# PandaSat_Payload.net
KiCad netlist of a schematic drawn in EAGLE
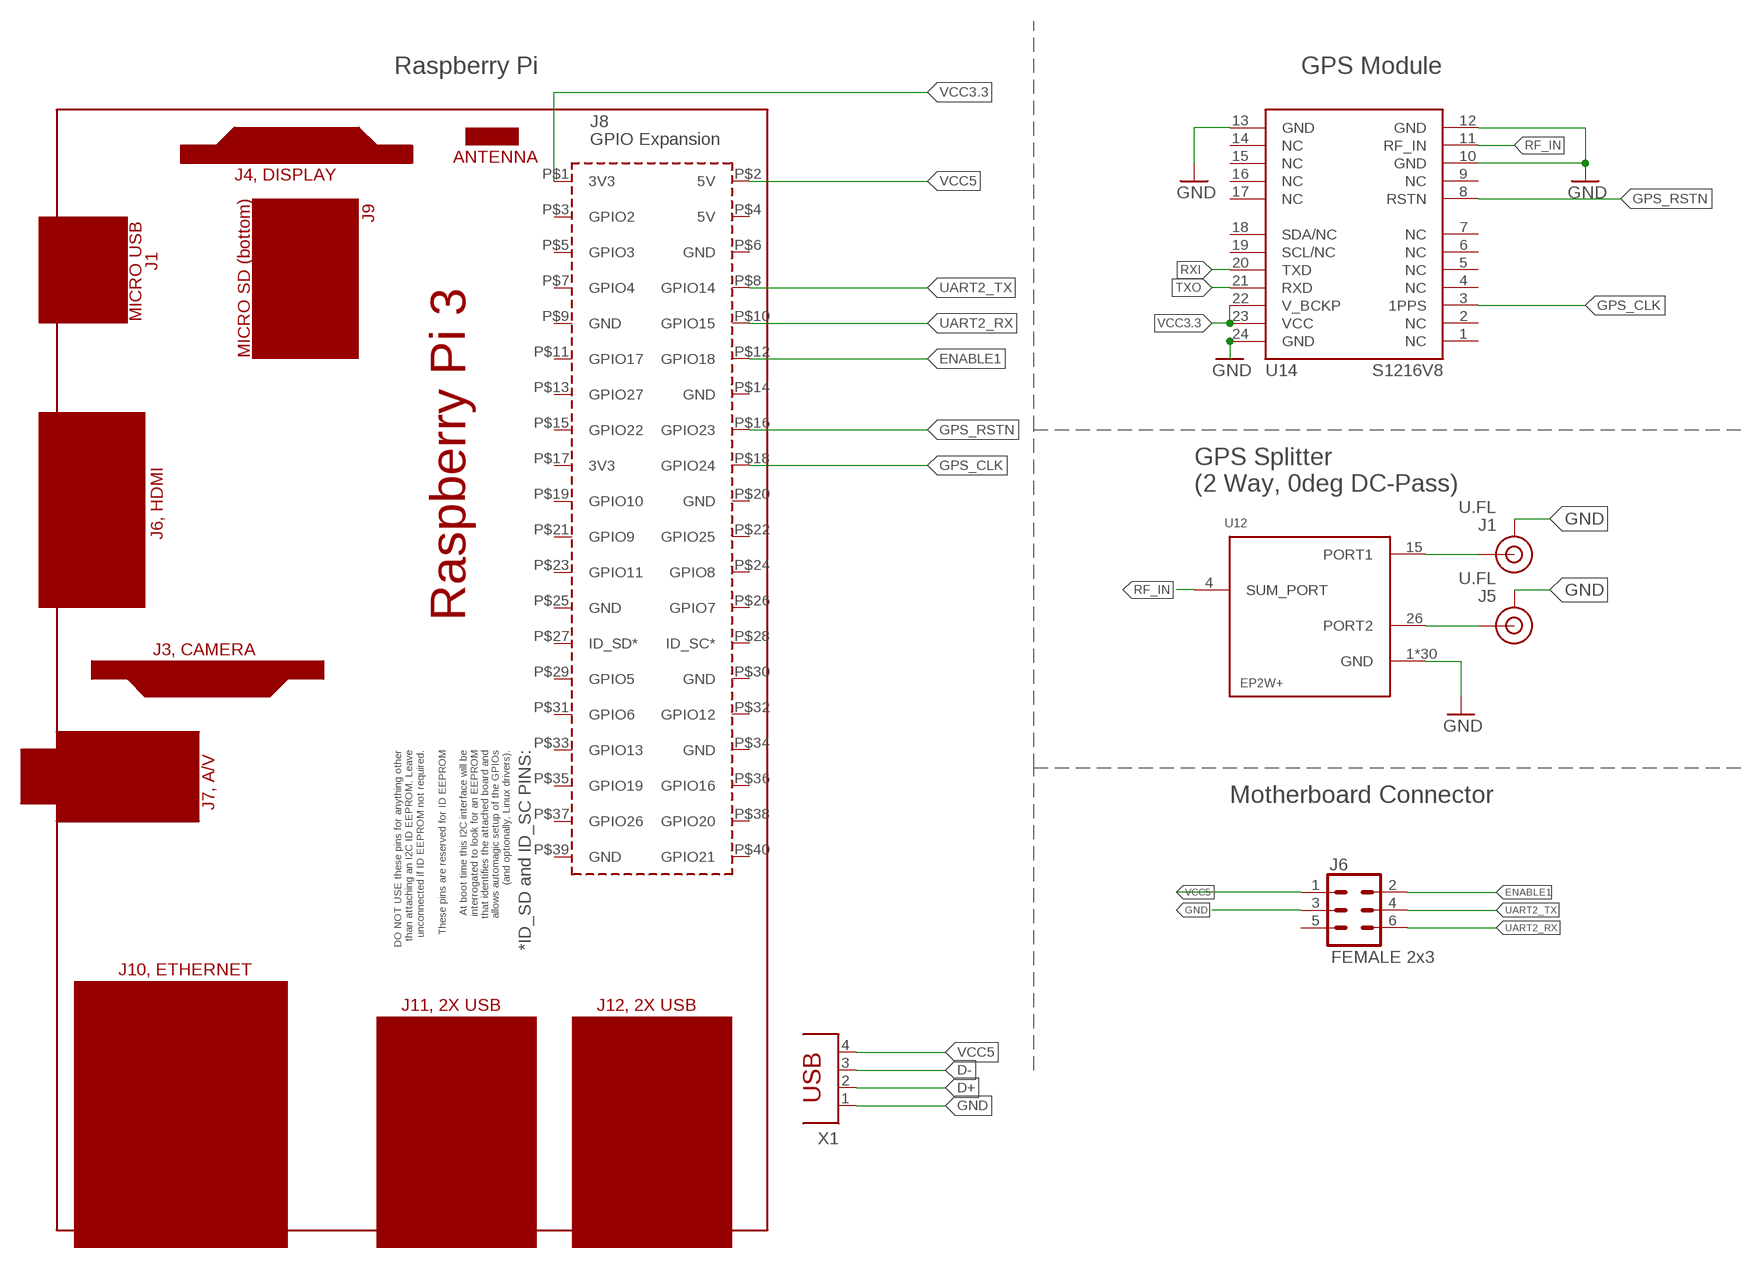
[diagram p0: schematic, sheet 1]
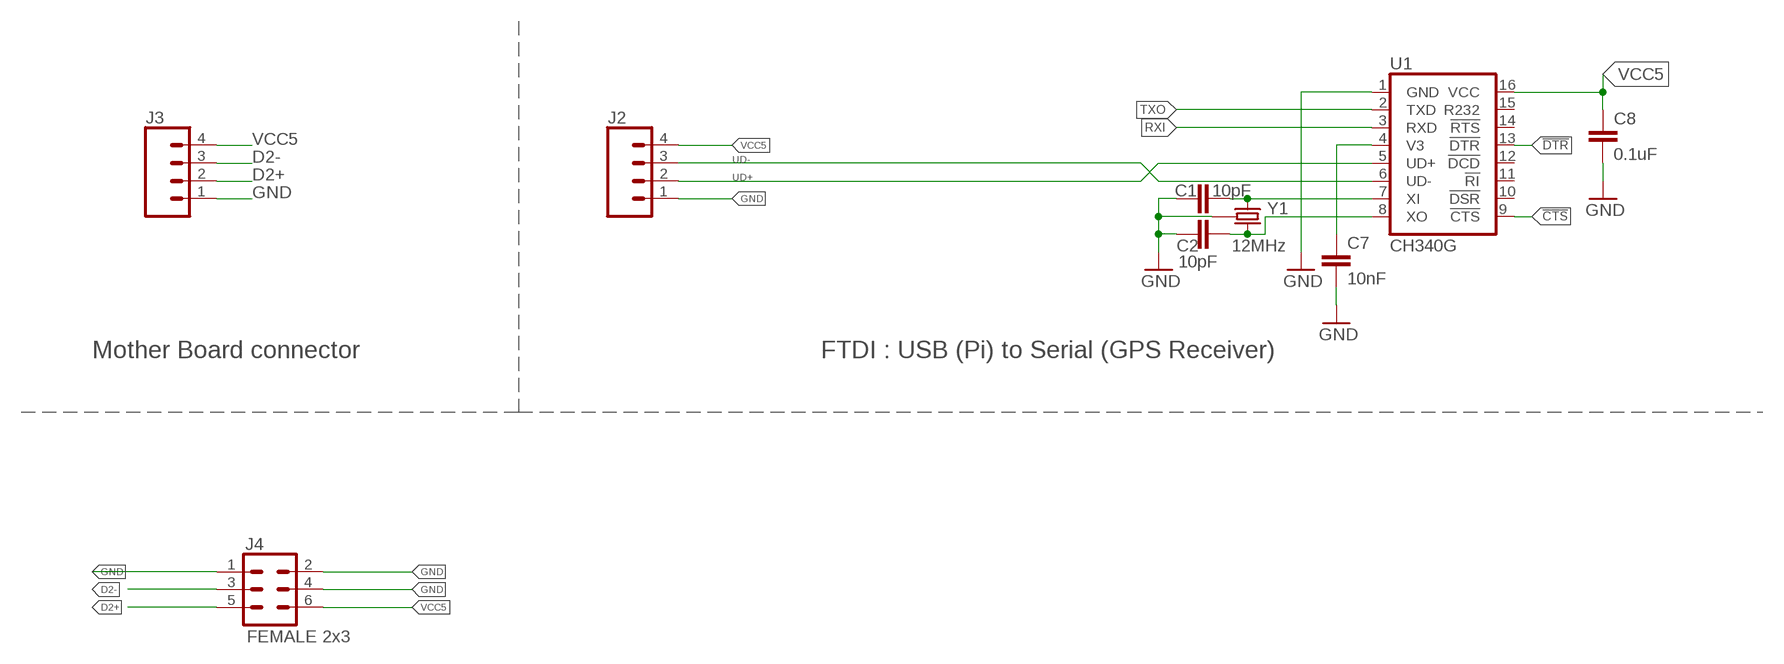
[diagram p1: schematic, sheet 2]

(export (version "E")
  (design (tool "Eeschema 10.0.6"))
  (components
    (comp (ref "J1")
      (value "U.FL")
      (footprint "eagle-import:U.FL")
      (libsource (lib "eagle-import") (part "U.FL2PIN"))
    )
    (comp (ref "J5")
      (value "U.FL")
      (footprint "eagle-import:U.FL")
      (libsource (lib "eagle-import") (part "U.FL2PIN"))
    )
    (comp (ref "J6")
      (value "FEMALE 2x3")
      (footprint "eagle-import:2X3")
      (libsource (lib "eagle-import") (part "CONN_03X2FEMALE"))
    )
    (comp (ref "PCB1")
      (value "RPI3RPI3")
      (footprint "eagle-import:RPI3")
      (libsource (lib "eagle-import") (part "RPI3RPI3"))
    )
    (comp (ref "U12")
      (value "EP2W+")
      (footprint "eagle-import:QFN32-5X5MM")
      (libsource (lib "eagle-import") (part "EP2W+"))
    )
    (comp (ref "U14")
      (value "S1216V8")
      (footprint "eagle-import:S1216_24PIN_PACKAGE")
      (libsource (lib "eagle-import") (part "S1216V8"))
    )
    (comp (ref "X1")
      (value "PN87520")
      (footprint "eagle-import:PN87520")
      (libsource (lib "eagle-import") (part "PN87520"))
    )
    (comp (ref "C1")
      (value "10pF")
      (footprint "eagle-import:0603-CAP")
      (libsource (lib "eagle-import") (part "10PF-50V-5%(0603)"))
    )
    (comp (ref "C2")
      (value "10pF")
      (footprint "eagle-import:0603-CAP")
      (libsource (lib "eagle-import") (part "10PF-50V-5%(0603)"))
    )
    (comp (ref "C7")
      (value "10nF")
      (footprint "eagle-import:0603-CAP")
      (libsource (lib "eagle-import") (part "10NF/10000PF-50V-10%(0603)"))
    )
    (comp (ref "C8")
      (value "0.1uF")
      (footprint "eagle-import:0603-CAP")
      (libsource (lib "eagle-import") (part "0.1UF-25V(+80/-20%)(0603)"))
    )
    (comp (ref "J2")
      (value "CONN_04")
      (footprint "eagle-import:1X04")
      (libsource (lib "eagle-import") (part "CONN_04"))
    )
    (comp (ref "J3")
      (value "CONN_04")
      (footprint "eagle-import:1X04")
      (libsource (lib "eagle-import") (part "CONN_04"))
    )
    (comp (ref "J4")
      (value "FEMALE 2x3")
      (footprint "eagle-import:2X3")
      (libsource (lib "eagle-import") (part "CONN_03X2FEMALE"))
    )
    (comp (ref "U1")
      (value "CH340G")
      (footprint "eagle-import:SO016")
      (libsource (lib "eagle-import") (part "CH340GSMD"))
    )
    (comp (ref "Y1")
      (value "12MHz")
      (footprint "eagle-import:CRYSTAL-SMD-3.2X2.5")
      (libsource (lib "eagle-import") (part "CRYSTAL-GROUNDED3.2X2.5"))
    )
  )
  (nets
    (net (code "1") (name "D+") (class "Default")
      (node (ref "X1") (pin "2") (pinfunction "2_2") (pintype "passive"))
    )
    (net (code "2") (name "D-") (class "Default")
      (node (ref "X1") (pin "3") (pinfunction "3_3") (pintype "passive"))
    )
    (net (code "3") (name "D2+") (class "Default")
      (node (ref "J3") (pin "2") (pinfunction "2_2") (pintype "passive"))
      (node (ref "J4") (pin "5") (pinfunction "5_5") (pintype "bidirectional"))
    )
    (net (code "4") (name "D2-") (class "Default")
      (node (ref "J3") (pin "3") (pinfunction "3_3") (pintype "passive"))
      (node (ref "J4") (pin "3") (pinfunction "3_3") (pintype "bidirectional"))
    )
    (net (code "5") (name "ENABLE1") (class "Default")
      (node (ref "J6") (pin "2") (pinfunction "2_2") (pintype "bidirectional"))
      (node (ref "PCB1") (pin "P$12") (pinfunction "GPIO18_P$12") (pintype "bidirectional"))
    )
    (net (code "6") (name "GND") (class "Default")
      (node (ref "C1") (pin "1") (pinfunction "1_1") (pintype "passive"))
      (node (ref "C2") (pin "1") (pinfunction "1_1") (pintype "passive"))
      (node (ref "C7") (pin "2") (pinfunction "2_2") (pintype "passive"))
      (node (ref "C8") (pin "2") (pinfunction "2_2") (pintype "passive"))
      (node (ref "J1") (pin "1") (pinfunction "GND_1") (pintype "bidirectional"))
      (node (ref "J1") (pin "2") (pinfunction "GND_2") (pintype "bidirectional"))
      (node (ref "J2") (pin "1") (pinfunction "1_1") (pintype "passive"))
      (node (ref "J3") (pin "1") (pinfunction "1_1") (pintype "passive"))
      (node (ref "J4") (pin "1") (pinfunction "1_1") (pintype "bidirectional"))
      (node (ref "J4") (pin "2") (pinfunction "2_2") (pintype "bidirectional"))
      (node (ref "J4") (pin "4") (pinfunction "4_4") (pintype "bidirectional"))
      (node (ref "J5") (pin "1") (pinfunction "GND_1") (pintype "bidirectional"))
      (node (ref "J5") (pin "2") (pinfunction "GND_2") (pintype "bidirectional"))
      (node (ref "J6") (pin "3") (pinfunction "3_3") (pintype "bidirectional"))
      (node (ref "U1") (pin "1") (pinfunction "GND_1") (pintype "bidirectional"))
      (node (ref "U12") (pin "1") (pinfunction "GND_1") (pintype "bidirectional"))
      (node (ref "U12") (pin "10") (pinfunction "GND_10") (pintype "bidirectional"))
      (node (ref "U12") (pin "11") (pinfunction "GND_11") (pintype "bidirectional"))
      (node (ref "U12") (pin "12") (pinfunction "GND_12") (pintype "bidirectional"))
      (node (ref "U12") (pin "13") (pinfunction "GND_13") (pintype "bidirectional"))
      (node (ref "U12") (pin "14") (pinfunction "GND_14") (pintype "bidirectional"))
      (node (ref "U12") (pin "16") (pinfunction "GND_16") (pintype "bidirectional"))
      (node (ref "U12") (pin "17") (pinfunction "GND_17") (pintype "bidirectional"))
      (node (ref "U12") (pin "18") (pinfunction "GND_18") (pintype "bidirectional"))
      (node (ref "U12") (pin "19") (pinfunction "GND_19") (pintype "bidirectional"))
      (node (ref "U12") (pin "2") (pinfunction "GND_2") (pintype "bidirectional"))
      (node (ref "U12") (pin "20") (pinfunction "GND_20") (pintype "bidirectional"))
      (node (ref "U12") (pin "21") (pinfunction "GND_21") (pintype "bidirectional"))
      (node (ref "U12") (pin "22") (pinfunction "GND_22") (pintype "bidirectional"))
      (node (ref "U12") (pin "23") (pinfunction "GND_23") (pintype "bidirectional"))
      (node (ref "U12") (pin "24") (pinfunction "GND_24") (pintype "bidirectional"))
      (node (ref "U12") (pin "25") (pinfunction "GND_25") (pintype "bidirectional"))
      (node (ref "U12") (pin "27") (pinfunction "GND_27") (pintype "bidirectional"))
      (node (ref "U12") (pin "28") (pinfunction "GND_28") (pintype "bidirectional"))
      (node (ref "U12") (pin "29") (pinfunction "GND_29") (pintype "bidirectional"))
      (node (ref "U12") (pin "3") (pinfunction "GND_3") (pintype "bidirectional"))
      (node (ref "U12") (pin "30") (pinfunction "GND_30") (pintype "bidirectional"))
      (node (ref "U12") (pin "31") (pinfunction "GND_31") (pintype "bidirectional"))
      (node (ref "U12") (pin "32") (pinfunction "GND_32") (pintype "bidirectional"))
      (node (ref "U12") (pin "5") (pinfunction "GND_5") (pintype "bidirectional"))
      (node (ref "U12") (pin "6") (pinfunction "GND_6") (pintype "bidirectional"))
      (node (ref "U12") (pin "7") (pinfunction "GND_7") (pintype "bidirectional"))
      (node (ref "U12") (pin "8") (pinfunction "GND_8") (pintype "bidirectional"))
      (node (ref "U12") (pin "9") (pinfunction "GND_9") (pintype "bidirectional"))
      (node (ref "U12") (pin "EP") (pinfunction "GND_EP") (pintype "bidirectional"))
      (node (ref "U14") (pin "10") (pinfunction "GND_10") (pintype "bidirectional"))
      (node (ref "U14") (pin "12") (pinfunction "GND_12") (pintype "bidirectional"))
      (node (ref "U14") (pin "13") (pinfunction "GND_13") (pintype "bidirectional"))
      (node (ref "U14") (pin "24") (pinfunction "GND_24") (pintype "bidirectional"))
      (node (ref "X1") (pin "1") (pinfunction "1_1") (pintype "passive"))
      (node (ref "Y1") (pin "2") (pinfunction "GND_2") (pintype "passive"))
      (node (ref "Y1") (pin "4") (pinfunction "GND_4") (pintype "passive"))
    )
    (net (code "7") (name "GPS_CLK") (class "Default")
      (node (ref "PCB1") (pin "P$18") (pinfunction "GPIO24_P$18") (pintype "bidirectional"))
      (node (ref "U14") (pin "3") (pinfunction "1PPS_3") (pintype "bidirectional"))
    )
    (net (code "8") (name "GPS_RSTN") (class "Default")
      (node (ref "PCB1") (pin "P$16") (pinfunction "GPIO23_P$16") (pintype "bidirectional"))
      (node (ref "U14") (pin "8") (pinfunction "RSTN_8") (pintype "bidirectional"))
    )
    (net (code "9") (name "Net-(J1-SIGNAL)") (class "Default")
      (node (ref "J1") (pin "FEED") (pinfunction "SIGNAL_FEED") (pintype "bidirectional"))
      (node (ref "U12") (pin "15") (pinfunction "PORT1_15") (pintype "bidirectional"))
    )
    (net (code "10") (name "Net-(J5-SIGNAL)") (class "Default")
      (node (ref "J5") (pin "FEED") (pinfunction "SIGNAL_FEED") (pintype "bidirectional"))
      (node (ref "U12") (pin "26") (pinfunction "PORT2_26") (pintype "bidirectional"))
    )
    (net (code "11") (name "Net-(U1-V3)") (class "Default")
      (node (ref "C7") (pin "1") (pinfunction "1_1") (pintype "passive"))
      (node (ref "U1") (pin "4") (pinfunction "V3_4") (pintype "bidirectional"))
    )
    (net (code "12") (name "Net-(U1-XI)") (class "Default")
      (node (ref "C1") (pin "2") (pinfunction "2_2") (pintype "passive"))
      (node (ref "U1") (pin "7") (pinfunction "XI_7") (pintype "bidirectional"))
      (node (ref "Y1") (pin "1") (pinfunction "1_1") (pintype "passive"))
    )
    (net (code "13") (name "Net-(U1-XO)") (class "Default")
      (node (ref "C2") (pin "2") (pinfunction "2_2") (pintype "passive"))
      (node (ref "U1") (pin "8") (pinfunction "XO_8") (pintype "bidirectional"))
      (node (ref "Y1") (pin "3") (pinfunction "2_3") (pintype "passive"))
    )
    (net (code "14") (name "RF_IN") (class "Default")
      (node (ref "U12") (pin "4") (pinfunction "SUM_PORT_4") (pintype "bidirectional"))
      (node (ref "U14") (pin "11") (pinfunction "RF_IN_11") (pintype "bidirectional"))
    )
    (net (code "15") (name "RXI") (class "Default")
      (node (ref "U1") (pin "3") (pinfunction "RXD_3") (pintype "bidirectional"))
      (node (ref "U14") (pin "20") (pinfunction "TXD_20") (pintype "bidirectional"))
    )
    (net (code "16") (name "TXO") (class "Default")
      (node (ref "U1") (pin "2") (pinfunction "TXD_2") (pintype "bidirectional"))
      (node (ref "U14") (pin "21") (pinfunction "RXD_21") (pintype "bidirectional"))
    )
    (net (code "17") (name "UART2_RX") (class "Default")
      (node (ref "J6") (pin "6") (pinfunction "6_6") (pintype "bidirectional"))
      (node (ref "PCB1") (pin "P$10") (pinfunction "GPIO15_P$10") (pintype "bidirectional"))
    )
    (net (code "18") (name "UART2_TX") (class "Default")
      (node (ref "J6") (pin "4") (pinfunction "4_4") (pintype "bidirectional"))
      (node (ref "PCB1") (pin "P$8") (pinfunction "GPIO14_P$8") (pintype "bidirectional"))
    )
    (net (code "19") (name "UD+") (class "Default")
      (node (ref "J2") (pin "2") (pinfunction "2_2") (pintype "passive"))
      (node (ref "U1") (pin "5") (pinfunction "UD+_5") (pintype "bidirectional"))
    )
    (net (code "20") (name "UD-") (class "Default")
      (node (ref "J2") (pin "3") (pinfunction "3_3") (pintype "passive"))
      (node (ref "U1") (pin "6") (pinfunction "UD-_6") (pintype "bidirectional"))
    )
    (net (code "21") (name "VCC3.3") (class "Default")
      (node (ref "PCB1") (pin "P$1") (pinfunction "3V3_P$1") (pintype "bidirectional"))
      (node (ref "U14") (pin "22") (pinfunction "V_BCKP_22") (pintype "bidirectional"))
      (node (ref "U14") (pin "23") (pinfunction "VCC_23") (pintype "bidirectional"))
    )
    (net (code "22") (name "VCC5") (class "Default")
      (node (ref "C8") (pin "1") (pinfunction "1_1") (pintype "passive"))
      (node (ref "J2") (pin "4") (pinfunction "4_4") (pintype "passive"))
      (node (ref "J3") (pin "4") (pinfunction "4_4") (pintype "passive"))
      (node (ref "J4") (pin "6") (pinfunction "6_6") (pintype "bidirectional"))
      (node (ref "J6") (pin "1") (pinfunction "1_1") (pintype "bidirectional"))
      (node (ref "PCB1") (pin "P$2") (pinfunction "5V_P$2") (pintype "bidirectional"))
      (node (ref "U1") (pin "16") (pinfunction "VCC_16") (pintype "bidirectional"))
      (node (ref "X1") (pin "4") (pinfunction "4_4") (pintype "passive"))
    )
    (net (code "23") (name "unconnected-(J6-Pad5)") (class "Default")
      (node (ref "J6") (pin "5") (pinfunction "5_5") (pintype "bidirectional"))
    )
    (net (code "24") (name "unconnected-(PCB1-3V3-PadP$17)") (class "Default")
      (node (ref "PCB1") (pin "P$17") (pinfunction "3V3_P$17") (pintype "bidirectional"))
    )
    (net (code "25") (name "unconnected-(PCB1-5V-PadP$4)") (class "Default")
      (node (ref "PCB1") (pin "P$4") (pinfunction "5V_P$4") (pintype "bidirectional"))
    )
    (net (code "26") (name "unconnected-(PCB1-GND-PadP$6)") (class "Default")
      (node (ref "PCB1") (pin "P$6") (pinfunction "GND_P$6") (pintype "bidirectional"))
    )
    (net (code "27") (name "unconnected-(PCB1-GND-PadP$9)") (class "Default")
      (node (ref "PCB1") (pin "P$9") (pinfunction "GND_P$9") (pintype "bidirectional"))
    )
    (net (code "28") (name "unconnected-(PCB1-GND-PadP$14)") (class "Default")
      (node (ref "PCB1") (pin "P$14") (pinfunction "GND_P$14") (pintype "bidirectional"))
    )
    (net (code "29") (name "unconnected-(PCB1-GND-PadP$20)") (class "Default")
      (node (ref "PCB1") (pin "P$20") (pinfunction "GND_P$20") (pintype "bidirectional"))
    )
    (net (code "30") (name "unconnected-(PCB1-GND-PadP$25)") (class "Default")
      (node (ref "PCB1") (pin "P$25") (pinfunction "GND_P$25") (pintype "bidirectional"))
    )
    (net (code "31") (name "unconnected-(PCB1-GND-PadP$30)") (class "Default")
      (node (ref "PCB1") (pin "P$30") (pinfunction "GND_P$30") (pintype "bidirectional"))
    )
    (net (code "32") (name "unconnected-(PCB1-GND-PadP$34)") (class "Default")
      (node (ref "PCB1") (pin "P$34") (pinfunction "GND_P$34") (pintype "bidirectional"))
    )
    (net (code "33") (name "unconnected-(PCB1-GND-PadP$39)") (class "Default")
      (node (ref "PCB1") (pin "P$39") (pinfunction "GND_P$39") (pintype "bidirectional"))
    )
    (net (code "34") (name "unconnected-(PCB1-GPIO2-PadP$3)") (class "Default")
      (node (ref "PCB1") (pin "P$3") (pinfunction "GPIO2_P$3") (pintype "bidirectional"))
    )
    (net (code "35") (name "unconnected-(PCB1-GPIO3-PadP$5)") (class "Default")
      (node (ref "PCB1") (pin "P$5") (pinfunction "GPIO3_P$5") (pintype "bidirectional"))
    )
    (net (code "36") (name "unconnected-(PCB1-GPIO4-PadP$7)") (class "Default")
      (node (ref "PCB1") (pin "P$7") (pinfunction "GPIO4_P$7") (pintype "bidirectional"))
    )
    (net (code "37") (name "unconnected-(PCB1-GPIO5-PadP$29)") (class "Default")
      (node (ref "PCB1") (pin "P$29") (pinfunction "GPIO5_P$29") (pintype "bidirectional"))
    )
    (net (code "38") (name "unconnected-(PCB1-GPIO6-PadP$31)") (class "Default")
      (node (ref "PCB1") (pin "P$31") (pinfunction "GPIO6_P$31") (pintype "bidirectional"))
    )
    (net (code "39") (name "unconnected-(PCB1-GPIO7-PadP$26)") (class "Default")
      (node (ref "PCB1") (pin "P$26") (pinfunction "GPIO7_P$26") (pintype "bidirectional"))
    )
    (net (code "40") (name "unconnected-(PCB1-GPIO8-PadP$24)") (class "Default")
      (node (ref "PCB1") (pin "P$24") (pinfunction "GPIO8_P$24") (pintype "bidirectional"))
    )
    (net (code "41") (name "unconnected-(PCB1-GPIO9-PadP$21)") (class "Default")
      (node (ref "PCB1") (pin "P$21") (pinfunction "GPIO9_P$21") (pintype "bidirectional"))
    )
    (net (code "42") (name "unconnected-(PCB1-GPIO10-PadP$19)") (class "Default")
      (node (ref "PCB1") (pin "P$19") (pinfunction "GPIO10_P$19") (pintype "bidirectional"))
    )
    (net (code "43") (name "unconnected-(PCB1-GPIO11-PadP$23)") (class "Default")
      (node (ref "PCB1") (pin "P$23") (pinfunction "GPIO11_P$23") (pintype "bidirectional"))
    )
    (net (code "44") (name "unconnected-(PCB1-GPIO12-PadP$32)") (class "Default")
      (node (ref "PCB1") (pin "P$32") (pinfunction "GPIO12_P$32") (pintype "bidirectional"))
    )
    (net (code "45") (name "unconnected-(PCB1-GPIO13-PadP$33)") (class "Default")
      (node (ref "PCB1") (pin "P$33") (pinfunction "GPIO13_P$33") (pintype "bidirectional"))
    )
    (net (code "46") (name "unconnected-(PCB1-GPIO16-PadP$36)") (class "Default")
      (node (ref "PCB1") (pin "P$36") (pinfunction "GPIO16_P$36") (pintype "bidirectional"))
    )
    (net (code "47") (name "unconnected-(PCB1-GPIO17-PadP$11)") (class "Default")
      (node (ref "PCB1") (pin "P$11") (pinfunction "GPIO17_P$11") (pintype "bidirectional"))
    )
    (net (code "48") (name "unconnected-(PCB1-GPIO19-PadP$35)") (class "Default")
      (node (ref "PCB1") (pin "P$35") (pinfunction "GPIO19_P$35") (pintype "bidirectional"))
    )
    (net (code "49") (name "unconnected-(PCB1-GPIO20-PadP$38)") (class "Default")
      (node (ref "PCB1") (pin "P$38") (pinfunction "GPIO20_P$38") (pintype "bidirectional"))
    )
    (net (code "50") (name "unconnected-(PCB1-GPIO21-PadP$40)") (class "Default")
      (node (ref "PCB1") (pin "P$40") (pinfunction "GPIO21_P$40") (pintype "bidirectional"))
    )
    (net (code "51") (name "unconnected-(PCB1-GPIO22-PadP$15)") (class "Default")
      (node (ref "PCB1") (pin "P$15") (pinfunction "GPIO22_P$15") (pintype "bidirectional"))
    )
    (net (code "52") (name "unconnected-(PCB1-GPIO25-PadP$22)") (class "Default")
      (node (ref "PCB1") (pin "P$22") (pinfunction "GPIO25_P$22") (pintype "bidirectional"))
    )
    (net (code "53") (name "unconnected-(PCB1-GPIO26-PadP$37)") (class "Default")
      (node (ref "PCB1") (pin "P$37") (pinfunction "GPIO26_P$37") (pintype "bidirectional"))
    )
    (net (code "54") (name "unconnected-(PCB1-GPIO27-PadP$13)") (class "Default")
      (node (ref "PCB1") (pin "P$13") (pinfunction "GPIO27_P$13") (pintype "bidirectional"))
    )
    (net (code "55") (name "unconnected-(PCB1-ID_SC*-PadP$28)") (class "Default")
      (node (ref "PCB1") (pin "P$28") (pinfunction "ID_SC*_P$28") (pintype "bidirectional"))
    )
    (net (code "56") (name "unconnected-(PCB1-ID_SD*-PadP$27)") (class "Default")
      (node (ref "PCB1") (pin "P$27") (pinfunction "ID_SD*_P$27") (pintype "bidirectional"))
    )
    (net (code "57") (name "unconnected-(U1-R232-Pad15)") (class "Default")
      (node (ref "U1") (pin "15") (pinfunction "R232_15") (pintype "bidirectional"))
    )
    (net (code "58") (name "unconnected-(U1-~{DCD}-Pad12)") (class "Default")
      (node (ref "U1") (pin "12") (pinfunction "~{DCD}_12") (pintype "bidirectional"))
    )
    (net (code "59") (name "unconnected-(U1-~{DSR}-Pad10)") (class "Default")
      (node (ref "U1") (pin "10") (pinfunction "~{DSR}_10") (pintype "bidirectional"))
    )
    (net (code "60") (name "unconnected-(U1-~{RI}-Pad11)") (class "Default")
      (node (ref "U1") (pin "11") (pinfunction "~{RI}_11") (pintype "bidirectional"))
    )
    (net (code "61") (name "unconnected-(U1-~{RTS}-Pad14)") (class "Default")
      (node (ref "U1") (pin "14") (pinfunction "~{RTS}_14") (pintype "bidirectional"))
    )
    (net (code "62") (name "unconnected-(U14-NC-Pad1)") (class "Default")
      (node (ref "U14") (pin "1") (pinfunction "NC_1") (pintype "bidirectional"))
    )
    (net (code "63") (name "unconnected-(U14-NC-Pad2)") (class "Default")
      (node (ref "U14") (pin "2") (pinfunction "NC_2") (pintype "bidirectional"))
    )
    (net (code "64") (name "unconnected-(U14-NC-Pad4)") (class "Default")
      (node (ref "U14") (pin "4") (pinfunction "NC_4") (pintype "bidirectional"))
    )
    (net (code "65") (name "unconnected-(U14-NC-Pad5)") (class "Default")
      (node (ref "U14") (pin "5") (pinfunction "NC_5") (pintype "bidirectional"))
    )
    (net (code "66") (name "unconnected-(U14-NC-Pad6)") (class "Default")
      (node (ref "U14") (pin "6") (pinfunction "NC_6") (pintype "bidirectional"))
    )
    (net (code "67") (name "unconnected-(U14-NC-Pad7)") (class "Default")
      (node (ref "U14") (pin "7") (pinfunction "NC_7") (pintype "bidirectional"))
    )
    (net (code "68") (name "unconnected-(U14-NC-Pad9)") (class "Default")
      (node (ref "U14") (pin "9") (pinfunction "NC_9") (pintype "bidirectional"))
    )
    (net (code "69") (name "unconnected-(U14-NC-Pad14)") (class "Default")
      (node (ref "U14") (pin "14") (pinfunction "NC_14") (pintype "bidirectional"))
    )
    (net (code "70") (name "unconnected-(U14-NC-Pad15)") (class "Default")
      (node (ref "U14") (pin "15") (pinfunction "NC_15") (pintype "bidirectional"))
    )
    (net (code "71") (name "unconnected-(U14-NC-Pad16)") (class "Default")
      (node (ref "U14") (pin "16") (pinfunction "NC_16") (pintype "bidirectional"))
    )
    (net (code "72") (name "unconnected-(U14-NC-Pad17)") (class "Default")
      (node (ref "U14") (pin "17") (pinfunction "NC_17") (pintype "bidirectional"))
    )
    (net (code "73") (name "unconnected-(U14-SCL{slash}NC-Pad19)") (class "Default")
      (node (ref "U14") (pin "19") (pinfunction "SCL/NC_19") (pintype "bidirectional"))
    )
    (net (code "74") (name "unconnected-(U14-SDA{slash}NC-Pad18)") (class "Default")
      (node (ref "U14") (pin "18") (pinfunction "SDA/NC_18") (pintype "bidirectional"))
    )
    (net (code "75") (name "~{CTS}") (class "Default")
      (node (ref "U1") (pin "9") (pinfunction "~{CTS}_9") (pintype "bidirectional"))
    )
    (net (code "76") (name "~{DTR}") (class "Default")
      (node (ref "U1") (pin "13") (pinfunction "~{DTR}_13") (pintype "bidirectional"))
    )
  )
)
